# Connectors.net
KiCad netlist of a schematic drawn in Altium Designer
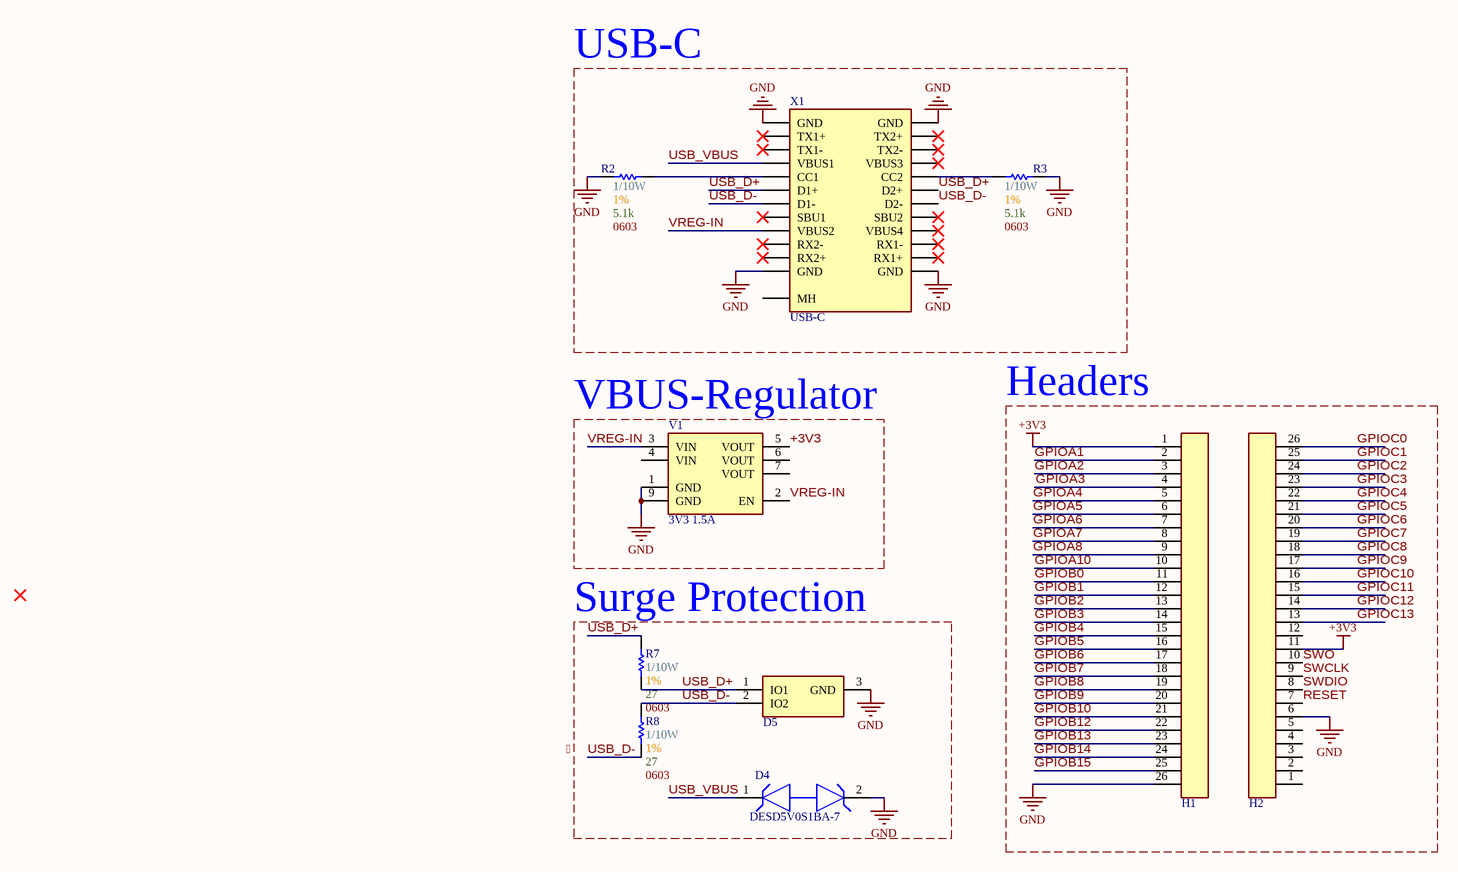
[diagram p0: Connectors.SchDoc]

(export (version "E")
  (design (tool "Eeschema 10.0.6"))
  (components
    (comp (ref "D4")
      (value "DESD5V0S1BA-7")
      (footprint "FP-SOD323-MFG")
      (description "TVS DIODE 5V 14V SOD323")
      (fields
        (field (name "MANUFACTURER") "Diodes Inc")
        (field (name "OCTOPART") "https://octopart.com/desd5v0s1ba-7-diodes+inc.-23272867")
      )
      (libsource (lib "Altium Content Vault") (part "7b0ed2e8f47950f6aa7ad67546d9f11"))
    )
    (comp (ref "D5")
      (value "TPD2E2U06QDBZRQ1")
      (footprint "SOT95P237X95-3N")
      (description "USB ESD Protection")
      (fields (field (name "MOUSER PART NUMBER") "595-TPD2E2U06QDBZRQ1"))
      (libsource (lib "Solar Gators") (part "TPD2E2U06QDBZRQ1"))
    )
    (comp (ref "H1")
      (value "1x26 Header")
      (footprint "[Header] 1x26 Male")
      (description "2.54mm pitch")
      (libsource (lib "") (part "[Header] 1x26 Male_1"))
    )
    (comp (ref "H2")
      (value "1x26 Header")
      (footprint "[Header] 1x26 Male")
      (description "2.54mm pitch")
      (libsource (lib "Connectors") (part "[Header] 1x26 Male"))
    )
    (comp (ref "R2")
      (value "[5.1k] SMD 0603 1% 1/10W")
      (footprint "[Res] SMD 0603")
      (description "RC0603FR-075K1L")
      (fields
        (field (name "WATTAGE") "1/10W")
        (field (name "TOLERANCE") "1%")
        (field (name "RESISTANCE") "5.1k")
        (field (name "SIZE PACKAGE") "0603")
      )
      (libsource (lib "Resistors") (part "[5.1k] SMD 0603 1% 1/10W"))
    )
    (comp (ref "R3")
      (value "[5.1k] SMD 0603 1% 1/10W")
      (footprint "[Res] SMD 0603")
      (description "RC0603FR-075K1L")
      (fields
        (field (name "WATTAGE") "1/10W")
        (field (name "TOLERANCE") "1%")
        (field (name "RESISTANCE") "5.1k")
        (field (name "SIZE PACKAGE") "0603")
      )
      (libsource (lib "Resistors") (part "[5.1k] SMD 0603 1% 1/10W"))
    )
    (comp (ref "R7")
      (value "[27] SMD 0603 1% 1/10W")
      (footprint "[Res] SMD 0603")
      (description "MCT06030C2709FP500")
      (fields
        (field (name "WATTAGE") "1/10W")
        (field (name "TOLERANCE") "1%")
        (field (name "RESISTANCE") "27")
        (field (name "SIZE PACKAGE") "0603")
      )
      (libsource (lib "Resistors") (part "[27] SMD 0603 1% 1/10W"))
    )
    (comp (ref "R8")
      (value "[27] SMD 0603 1% 1/10W")
      (footprint "[Res] SMD 0603")
      (description "MCT06030C2709FP500")
      (fields
        (field (name "WATTAGE") "1/10W")
        (field (name "TOLERANCE") "1%")
        (field (name "RESISTANCE") "27")
        (field (name "SIZE PACKAGE") "0603")
      )
      (libsource (lib "Resistors") (part "[27] SMD 0603 1% 1/10W"))
    )
    (comp (ref "V1")
      (value "3V3 1.5A")
      (footprint "[Linear] 3V3 1.5A")
      (description "AP7362A-33SP-13")
      (libsource (lib "Voltage Regulators") (part "[Linear] 3V3 1.5A"))
    )
    (comp (ref "X1")
      (value "USB-C")
      (footprint "[USB] USB-C Right-Angle")
      (libsource (lib "Connectors") (part "[USB] Type-C Right-Angle"))
    )
  )
  (nets
    (net (code "1") (name "+3V3") (class "Default")
      (node (ref "H1") (pin "1") (pinfunction "1_1") (pintype "passive"))
      (node (ref "H2") (pin "11") (pinfunction "11_11") (pintype "passive"))
      (node (ref "V1") (pin "5") (pinfunction "VOUT_5") (pintype "passive"))
    )
    (net (code "3") (name "/GPIOA1") (class "Default")
      (node (ref "H1") (pin "2") (pinfunction "2_2") (pintype "passive"))
    )
    (net (code "4") (name "/GPIOA2") (class "Default")
      (node (ref "H1") (pin "3") (pinfunction "3_3") (pintype "passive"))
    )
    (net (code "5") (name "/GPIOA3") (class "Default")
      (node (ref "H1") (pin "4") (pinfunction "4_4") (pintype "passive"))
    )
    (net (code "6") (name "/GPIOA4") (class "Default")
      (node (ref "H1") (pin "5") (pinfunction "5_5") (pintype "passive"))
    )
    (net (code "7") (name "/GPIOA5") (class "Default")
      (node (ref "H1") (pin "6") (pinfunction "6_6") (pintype "passive"))
    )
    (net (code "8") (name "/GPIOA6") (class "Default")
      (node (ref "H1") (pin "7") (pinfunction "7_7") (pintype "passive"))
    )
    (net (code "9") (name "/GPIOA7") (class "Default")
      (node (ref "H1") (pin "8") (pinfunction "8_8") (pintype "passive"))
    )
    (net (code "10") (name "/GPIOA8") (class "Default")
      (node (ref "H1") (pin "9") (pinfunction "9_9") (pintype "passive"))
    )
    (net (code "11") (name "/GPIOA10") (class "Default")
      (node (ref "H1") (pin "10") (pinfunction "10_10") (pintype "passive"))
    )
    (net (code "12") (name "/GPIOB0") (class "Default")
      (node (ref "H1") (pin "11") (pinfunction "11_11") (pintype "passive"))
    )
    (net (code "13") (name "/GPIOB1") (class "Default")
      (node (ref "H1") (pin "12") (pinfunction "12_12") (pintype "passive"))
    )
    (net (code "14") (name "/GPIOB2") (class "Default")
      (node (ref "H1") (pin "13") (pinfunction "13_13") (pintype "passive"))
    )
    (net (code "15") (name "/GPIOB3") (class "Default")
      (node (ref "H1") (pin "14") (pinfunction "14_14") (pintype "passive"))
    )
    (net (code "16") (name "/GPIOB4") (class "Default")
      (node (ref "H1") (pin "15") (pinfunction "15_15") (pintype "passive"))
    )
    (net (code "17") (name "/GPIOB5") (class "Default")
      (node (ref "H1") (pin "16") (pinfunction "16_16") (pintype "passive"))
    )
    (net (code "18") (name "/GPIOB6") (class "Default")
      (node (ref "H1") (pin "17") (pinfunction "17_17") (pintype "passive"))
    )
    (net (code "19") (name "/GPIOB7") (class "Default")
      (node (ref "H1") (pin "18") (pinfunction "18_18") (pintype "passive"))
    )
    (net (code "20") (name "/GPIOB8") (class "Default")
      (node (ref "H1") (pin "19") (pinfunction "19_19") (pintype "passive"))
    )
    (net (code "21") (name "/GPIOB9") (class "Default")
      (node (ref "H1") (pin "20") (pinfunction "20_20") (pintype "passive"))
    )
    (net (code "22") (name "/GPIOB10") (class "Default")
      (node (ref "H1") (pin "21") (pinfunction "21_21") (pintype "passive"))
    )
    (net (code "23") (name "/GPIOB12") (class "Default")
      (node (ref "H1") (pin "22") (pinfunction "22_22") (pintype "passive"))
    )
    (net (code "24") (name "/GPIOB13") (class "Default")
      (node (ref "H1") (pin "23") (pinfunction "23_23") (pintype "passive"))
    )
    (net (code "25") (name "/GPIOB14") (class "Default")
      (node (ref "H1") (pin "24") (pinfunction "24_24") (pintype "passive"))
    )
    (net (code "26") (name "/GPIOB15") (class "Default")
      (node (ref "H1") (pin "25") (pinfunction "25_25") (pintype "passive"))
    )
    (net (code "27") (name "/GPIOC0") (class "Default")
      (node (ref "H2") (pin "26") (pinfunction "26_26") (pintype "passive"))
    )
    (net (code "28") (name "/GPIOC1") (class "Default")
      (node (ref "H2") (pin "25") (pinfunction "25_25") (pintype "passive"))
    )
    (net (code "29") (name "/GPIOC2") (class "Default")
      (node (ref "H2") (pin "24") (pinfunction "24_24") (pintype "passive"))
    )
    (net (code "30") (name "/GPIOC3") (class "Default")
      (node (ref "H2") (pin "23") (pinfunction "23_23") (pintype "passive"))
    )
    (net (code "31") (name "/GPIOC4") (class "Default")
      (node (ref "H2") (pin "22") (pinfunction "22_22") (pintype "passive"))
    )
    (net (code "32") (name "/GPIOC5") (class "Default")
      (node (ref "H2") (pin "21") (pinfunction "21_21") (pintype "passive"))
    )
    (net (code "33") (name "/GPIOC6") (class "Default")
      (node (ref "H2") (pin "20") (pinfunction "20_20") (pintype "passive"))
    )
    (net (code "34") (name "/GPIOC7") (class "Default")
      (node (ref "H2") (pin "19") (pinfunction "19_19") (pintype "passive"))
    )
    (net (code "35") (name "/GPIOC8") (class "Default")
      (node (ref "H2") (pin "18") (pinfunction "18_18") (pintype "passive"))
    )
    (net (code "36") (name "/GPIOC9") (class "Default")
      (node (ref "H2") (pin "17") (pinfunction "17_17") (pintype "passive"))
    )
    (net (code "37") (name "/GPIOC10") (class "Default")
      (node (ref "H2") (pin "16") (pinfunction "16_16") (pintype "passive"))
    )
    (net (code "38") (name "/GPIOC11") (class "Default")
      (node (ref "H2") (pin "15") (pinfunction "15_15") (pintype "passive"))
    )
    (net (code "39") (name "/GPIOC12") (class "Default")
      (node (ref "H2") (pin "14") (pinfunction "14_14") (pintype "passive"))
    )
    (net (code "40") (name "/GPIOC13") (class "Default")
      (node (ref "H2") (pin "13") (pinfunction "13_13") (pintype "passive"))
    )
    (net (code "41") (name "/RESET") (class "Default")
      (node (ref "H2") (pin "7") (pinfunction "7_7") (pintype "passive"))
    )
    (net (code "42") (name "/SWCLK") (class "Default")
      (node (ref "H2") (pin "9") (pinfunction "9_9") (pintype "passive"))
    )
    (net (code "43") (name "/SWDIO") (class "Default")
      (node (ref "H2") (pin "8") (pinfunction "8_8") (pintype "passive"))
    )
    (net (code "44") (name "/SWO") (class "Default")
      (node (ref "H2") (pin "10") (pinfunction "10_10") (pintype "passive"))
    )
    (net (code "45") (name "/USB_D+") (class "Default")
      (node (ref "D5") (pin "1") (pinfunction "IO1_1") (pintype "passive"))
      (node (ref "R7") (pin "1") (pinfunction "1_1") (pintype "passive"))
      (node (ref "R7") (pin "2") (pinfunction "2_2") (pintype "passive"))
      (node (ref "X1") (pin "A6") (pinfunction "D1+_A6") (pintype "passive"))
      (node (ref "X1") (pin "B6") (pinfunction "D2+_B6") (pintype "passive"))
    )
    (net (code "46") (name "/USB_D-") (class "Default")
      (node (ref "D5") (pin "2") (pinfunction "IO2_2") (pintype "passive"))
      (node (ref "R8") (pin "1") (pinfunction "1_1") (pintype "passive"))
      (node (ref "R8") (pin "2") (pinfunction "2_2") (pintype "passive"))
      (node (ref "X1") (pin "A7") (pinfunction "D1-_A7") (pintype "passive"))
      (node (ref "X1") (pin "B7") (pinfunction "D2-_B7") (pintype "passive"))
    )
    (net (code "47") (name "/USB_VBUS") (class "Default")
      (node (ref "D4") (pin "1") (pinfunction "1_1") (pintype "passive"))
      (node (ref "X1") (pin "A4") (pinfunction "VBUS1_A4") (pintype "passive"))
    )
    (net (code "48") (name "/VREG-IN") (class "Default")
      (node (ref "V1") (pin "2") (pinfunction "EN_2") (pintype "passive"))
      (node (ref "V1") (pin "3") (pinfunction "VIN_3") (pintype "passive"))
      (node (ref "X1") (pin "A9") (pinfunction "VBUS2_A9") (pintype "passive"))
    )
    (net (code "49") (name "GND") (class "Default")
      (node (ref "D4") (pin "2") (pinfunction "2_2") (pintype "passive"))
      (node (ref "D5") (pin "3") (pinfunction "GND_3") (pintype "power_in"))
      (node (ref "H1") (pin "26") (pinfunction "26_26") (pintype "passive"))
      (node (ref "H2") (pin "6") (pinfunction "6_6") (pintype "passive"))
      (node (ref "R2") (pin "1") (pinfunction "1_1") (pintype "passive"))
      (node (ref "R3") (pin "2") (pinfunction "2_2") (pintype "passive"))
      (node (ref "V1") (pin "1") (pinfunction "GND_1") (pintype "passive"))
      (node (ref "V1") (pin "9") (pinfunction "GND_9") (pintype "passive"))
      (node (ref "X1") (pin "A1") (pinfunction "GND_A1") (pintype "passive"))
      (node (ref "X1") (pin "A12") (pinfunction "GND_A12") (pintype "passive"))
      (node (ref "X1") (pin "B1") (pinfunction "GND_B1") (pintype "passive"))
      (node (ref "X1") (pin "B12") (pinfunction "GND_B12") (pintype "passive"))
    )
    (net (code "50") (name "Net-(X1-CC1)") (class "Default")
      (node (ref "R2") (pin "2") (pinfunction "2_2") (pintype "passive"))
      (node (ref "X1") (pin "A5") (pinfunction "CC1_A5") (pintype "passive"))
    )
    (net (code "51") (name "Net-(X1-CC2)") (class "Default")
      (node (ref "R3") (pin "1") (pinfunction "1_1") (pintype "passive"))
      (node (ref "X1") (pin "B5") (pinfunction "CC2_B5") (pintype "passive"))
    )
    (net (code "52") (name "unconnected-(H2-Pad1)") (class "Default")
      (node (ref "H2") (pin "1") (pinfunction "1_1") (pintype "passive"))
    )
    (net (code "53") (name "unconnected-(H2-Pad2)") (class "Default")
      (node (ref "H2") (pin "2") (pinfunction "2_2") (pintype "passive"))
    )
    (net (code "54") (name "unconnected-(H2-Pad3)") (class "Default")
      (node (ref "H2") (pin "3") (pinfunction "3_3") (pintype "passive"))
    )
    (net (code "55") (name "unconnected-(H2-Pad4)") (class "Default")
      (node (ref "H2") (pin "4") (pinfunction "4_4") (pintype "passive"))
    )
    (net (code "56") (name "unconnected-(H2-Pad5)") (class "Default")
      (node (ref "H2") (pin "5") (pinfunction "5_5") (pintype "passive"))
    )
    (net (code "57") (name "unconnected-(H2-Pad12)") (class "Default")
      (node (ref "H2") (pin "12") (pinfunction "12_12") (pintype "passive"))
    )
    (net (code "58") (name "unconnected-(V1-VIN-Pad4)") (class "Default")
      (node (ref "V1") (pin "4") (pinfunction "VIN_4") (pintype "passive"))
    )
    (net (code "59") (name "unconnected-(V1-VOUT-Pad6)") (class "Default")
      (node (ref "V1") (pin "6") (pinfunction "VOUT_6") (pintype "passive"))
    )
    (net (code "60") (name "unconnected-(V1-VOUT-Pad7)") (class "Default")
      (node (ref "V1") (pin "7") (pinfunction "VOUT_7") (pintype "passive"))
    )
    (net (code "61") (name "unconnected-(X1-PadMH)") (class "Default")
      (node (ref "X1") (pin "MH") (pinfunction "MH_MH") (pintype "passive"))
    )
    (net (code "62") (name "unconnected-(X1-RX1+-PadB11)") (class "Default")
      (node (ref "X1") (pin "B11") (pinfunction "RX1+_B11") (pintype "passive+no_connect"))
    )
    (net (code "63") (name "unconnected-(X1-RX1--PadB10)") (class "Default")
      (node (ref "X1") (pin "B10") (pinfunction "RX1-_B10") (pintype "passive+no_connect"))
    )
    (net (code "64") (name "unconnected-(X1-RX2+-PadA11)") (class "Default")
      (node (ref "X1") (pin "A11") (pinfunction "RX2+_A11") (pintype "passive+no_connect"))
    )
    (net (code "65") (name "unconnected-(X1-RX2--PadA10)") (class "Default")
      (node (ref "X1") (pin "A10") (pinfunction "RX2-_A10") (pintype "passive+no_connect"))
    )
    (net (code "66") (name "unconnected-(X1-SBU1-PadA8)") (class "Default")
      (node (ref "X1") (pin "A8") (pinfunction "SBU1_A8") (pintype "passive+no_connect"))
    )
    (net (code "67") (name "unconnected-(X1-SBU2-PadB8)") (class "Default")
      (node (ref "X1") (pin "B8") (pinfunction "SBU2_B8") (pintype "passive+no_connect"))
    )
    (net (code "68") (name "unconnected-(X1-TX1+-PadA2)") (class "Default")
      (node (ref "X1") (pin "A2") (pinfunction "TX1+_A2") (pintype "passive+no_connect"))
    )
    (net (code "69") (name "unconnected-(X1-TX1--PadA3)") (class "Default")
      (node (ref "X1") (pin "A3") (pinfunction "TX1-_A3") (pintype "passive+no_connect"))
    )
    (net (code "70") (name "unconnected-(X1-TX2+-PadB2)") (class "Default")
      (node (ref "X1") (pin "B2") (pinfunction "TX2+_B2") (pintype "passive+no_connect"))
    )
    (net (code "71") (name "unconnected-(X1-TX2--PadB3)") (class "Default")
      (node (ref "X1") (pin "B3") (pinfunction "TX2-_B3") (pintype "passive+no_connect"))
    )
    (net (code "72") (name "unconnected-(X1-VBUS3-PadB4)") (class "Default")
      (node (ref "X1") (pin "B4") (pinfunction "VBUS3_B4") (pintype "passive+no_connect"))
    )
    (net (code "73") (name "unconnected-(X1-VBUS4-PadB9)") (class "Default")
      (node (ref "X1") (pin "B9") (pinfunction "VBUS4_B9") (pintype "passive+no_connect"))
    )
  )
)
